# phantom_power_enabler.net
KiCad netlist of a schematic drawn in Altium Designer
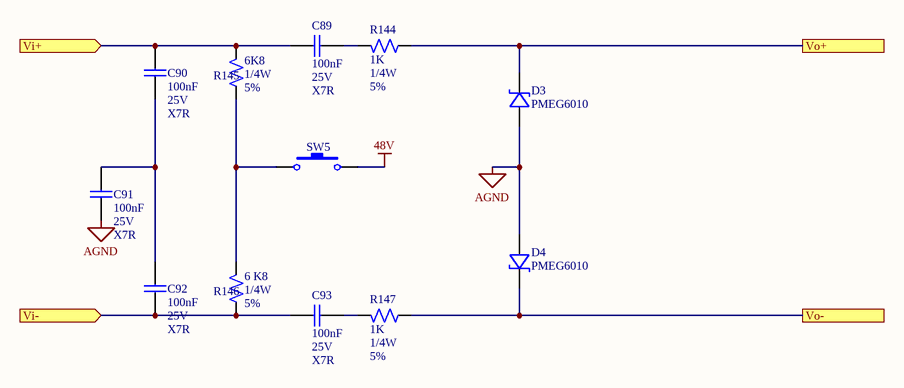
[diagram p0: phantom_power_enabler.SchDoc]

(export (version "E")
  (design (tool "Eeschema 10.0.6"))
  (components
    (comp (ref "C89")
      (value "Capacitor")
      (footprint "C0805")
      (description "Capacitor de placas paralelas")
      (fields (field (name "VALOR") "100nF") (field (name "TENSION") "25V") (field (name "TOLERANCIA") "X7R"))
      (libsource (lib "Sch_Comunes") (part "Capacitor"))
    )
    (comp (ref "C90")
      (value "Capacitor")
      (footprint "C0805")
      (description "Capacitor de placas paralelas")
      (fields (field (name "VALOR") "100nF") (field (name "TENSION") "25V") (field (name "TOLERANCIA") "X7R"))
      (libsource (lib "Sch_Comunes") (part "Capacitor"))
    )
    (comp (ref "C91")
      (value "Capacitor")
      (footprint "C0805")
      (description "Capacitor de placas paralelas")
      (fields (field (name "VALOR") "100nF") (field (name "TENSION") "25V") (field (name "TOLERANCIA") "X7R"))
      (libsource (lib "Sch_Comunes") (part "Capacitor"))
    )
    (comp (ref "C92")
      (value "Capacitor")
      (footprint "C0805")
      (description "Capacitor de placas paralelas")
      (fields (field (name "VALOR") "100nF") (field (name "TENSION") "25V") (field (name "TOLERANCIA") "X7R"))
      (libsource (lib "Sch_Comunes") (part "Capacitor"))
    )
    (comp (ref "C93")
      (value "Capacitor")
      (footprint "C0805")
      (description "Capacitor de placas paralelas")
      (fields (field (name "VALOR") "100nF") (field (name "TENSION") "25V") (field (name "TOLERANCIA") "X7R"))
      (libsource (lib "Sch_Comunes") (part "Capacitor"))
    )
    (comp (ref "D3")
      (value "PMEG6010")
      (footprint "SOD128")
      (libsource (lib "sch_comunes") (part "Schottky Diode"))
    )
    (comp (ref "D4")
      (value "PMEG6010")
      (footprint "SOD128")
      (libsource (lib "sch_comunes") (part "Schottky Diode"))
    )
    (comp (ref "R144")
      (value "Resistor")
      (footprint "R0805")
      (description "Resistencia")
      (fields (field (name "VALOR") "1K") (field (name "POTENCIA") "1/4W") (field (name "TOLERANCIA") "5%"))
      (libsource (lib "sch_comunes") (part "Resistor"))
    )
    (comp (ref "R145")
      (value "Resistor")
      (footprint "R0805")
      (description "Resistencia")
      (fields (field (name "VALOR") "6K8") (field (name "POTENCIA") "1/4W") (field (name "TOLERANCIA") "5%"))
      (libsource (lib "sch_comunes") (part "Resistor"))
    )
    (comp (ref "R146")
      (value "Resistor")
      (footprint "R0805")
      (description "Resistencia")
      (fields (field (name "VALOR") "6 K8") (field (name "POTENCIA") "1/4W") (field (name "TOLERANCIA") "5%"))
      (libsource (lib "sch_comunes") (part "Resistor"))
    )
    (comp (ref "R147")
      (value "Resistor")
      (footprint "R0805")
      (description "Resistencia")
      (fields (field (name "VALOR") "1K") (field (name "POTENCIA") "1/4W") (field (name "TOLERANCIA") "5%"))
      (libsource (lib "sch_comunes") (part "Resistor"))
    )
    (comp (ref "SW5")
      (value "TAC_SWITCH_4")
      (footprint "Header 2x1")
      (description "Pulsador de 4 pines")
      (libsource (lib "sch_comunes") (part "TAC_SWITCH_4"))
    )
  )
  (nets
    (net (code "1") (name "/Vi+") (class "Default")
      (node (ref "C89") (pin "1") (pinfunction "1_1") (pintype "passive"))
      (node (ref "C90") (pin "1") (pinfunction "1_1") (pintype "passive"))
      (node (ref "R145") (pin "2") (pinfunction "2_2") (pintype "passive"))
    )
    (net (code "2") (name "/Vi-") (class "Default")
      (node (ref "C92") (pin "2") (pinfunction "2_2") (pintype "passive"))
      (node (ref "C93") (pin "1") (pinfunction "1_1") (pintype "passive"))
      (node (ref "R146") (pin "1") (pinfunction "1_1") (pintype "passive"))
    )
    (net (code "3") (name "/Vo+") (class "Default")
      (node (ref "D3") (pin "1") (pintype "passive"))
      (node (ref "R144") (pin "1") (pinfunction "1_1") (pintype "passive"))
    )
    (net (code "4") (name "/Vo-") (class "Default")
      (node (ref "D4") (pin "1") (pintype "passive"))
      (node (ref "R147") (pin "1") (pinfunction "1_1") (pintype "passive"))
    )
    (net (code "5") (name "48V") (class "Default")
      (node (ref "SW5") (pin "2") (pinfunction "2_2") (pintype "passive"))
    )
    (net (code "6") (name "AGND") (class "Default")
      (node (ref "C91") (pin "2") (pinfunction "2_2") (pintype "passive"))
      (node (ref "D3") (pin "2") (pintype "passive"))
      (node (ref "D4") (pin "2") (pintype "passive"))
    )
    (net (code "7") (name "Net-(C89-Pad2)") (class "Default")
      (node (ref "C89") (pin "2") (pinfunction "2_2") (pintype "passive"))
      (node (ref "R144") (pin "2") (pinfunction "2_2") (pintype "passive"))
    )
    (net (code "8") (name "Net-(C90-Pad2)") (class "Default")
      (node (ref "C90") (pin "2") (pinfunction "2_2") (pintype "passive"))
      (node (ref "C91") (pin "1") (pinfunction "1_1") (pintype "passive"))
      (node (ref "C92") (pin "1") (pinfunction "1_1") (pintype "passive"))
    )
    (net (code "9") (name "Net-(C93-Pad2)") (class "Default")
      (node (ref "C93") (pin "2") (pinfunction "2_2") (pintype "passive"))
      (node (ref "R147") (pin "2") (pinfunction "2_2") (pintype "passive"))
    )
    (net (code "10") (name "Net-(R145-Pad1)") (class "Default")
      (node (ref "R145") (pin "1") (pinfunction "1_1") (pintype "passive"))
      (node (ref "R146") (pin "2") (pinfunction "2_2") (pintype "passive"))
      (node (ref "SW5") (pin "1") (pinfunction "1_1") (pintype "passive"))
    )
  )
)
